# OutputPort.net
KiCad netlist of a schematic drawn in Altium Designer
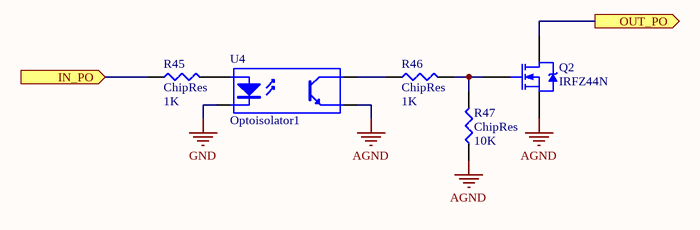
[diagram p0: OutputPort.SchDoc]

(export (version "E")
  (design (tool "Eeschema 10.0.6"))
  (components
    (comp (ref "Q2")
      (value "IRFZ44N")
      (footprint "TO-220AB")
      (description "HEXFET Power MOSFET")
      (fields (field (name "PUBLISHER") "Altium Limited"))
      (libsource (lib "IR Discrete MOSFET - Power") (part "IRFZ44N"))
    )
    (comp (ref "R45")
      (value "ChipRes")
      (footprint "RES0805")
      (description "Chip resistor")
      (fields (field (name "ALTIUM_VALUE") "1K"))
      (libsource (lib "Common Devices") (part "ChipRes"))
    )
    (comp (ref "R46")
      (value "ChipRes")
      (footprint "RES0805")
      (description "Chip resistor")
      (fields (field (name "ALTIUM_VALUE") "1K"))
      (libsource (lib "Common Devices") (part "ChipRes"))
    )
    (comp (ref "R47")
      (value "ChipRes")
      (footprint "RES0805")
      (description "Chip resistor")
      (fields (field (name "ALTIUM_VALUE") "10K"))
      (libsource (lib "Common Devices") (part "ChipRes"))
    )
    (comp (ref "U4")
      (value "Optoisolator1")
      (footprint "DIP-4")
      (description "4-Pin Phototransistor Optocoupler")
      (fields (field (name "PUBLISHER") "Altium Limited"))
      (libsource (lib "Miscellaneous Devices") (part "Optoisolator1"))
    )
  )
  (nets
    (net (code "1") (name "/IN_PO") (class "Default") (node (ref "R45") (pin "1") (pintype "passive")))
    (net (code "2") (name "/OUT_PO") (class "Default")
      (node (ref "Q2") (pin "2") (pinfunction "D_2") (pintype "passive"))
    )
    (net (code "3") (name "AGND") (class "Default")
      (node (ref "Q2") (pin "3") (pinfunction "S_3") (pintype "passive"))
      (node (ref "R47") (pin "1") (pintype "passive"))
      (node (ref "U4") (pin "3") (pinfunction "E_3") (pintype "passive"))
    )
    (net (code "4") (name "GND") (class "Default")
      (node (ref "U4") (pin "2") (pinfunction "K_2") (pintype "passive"))
    )
    (net (code "5") (name "Net-(Q2-G)") (class "Default")
      (node (ref "Q2") (pin "1") (pinfunction "G_1") (pintype "passive"))
      (node (ref "R46") (pin "2") (pintype "passive"))
      (node (ref "R47") (pin "2") (pintype "passive"))
    )
    (net (code "6") (name "Net-(U4-A)") (class "Default")
      (node (ref "R45") (pin "2") (pintype "passive"))
      (node (ref "U4") (pin "1") (pinfunction "A_1") (pintype "passive"))
    )
    (net (code "7") (name "Net-(U4-C)") (class "Default")
      (node (ref "R46") (pin "1") (pintype "passive"))
      (node (ref "U4") (pin "4") (pinfunction "C_4") (pintype "passive"))
    )
  )
)
